# lm3410-sepic-rgb-led-driver-tester-mk-1.net
KiCad netlist of a schematic drawn in EAGLE
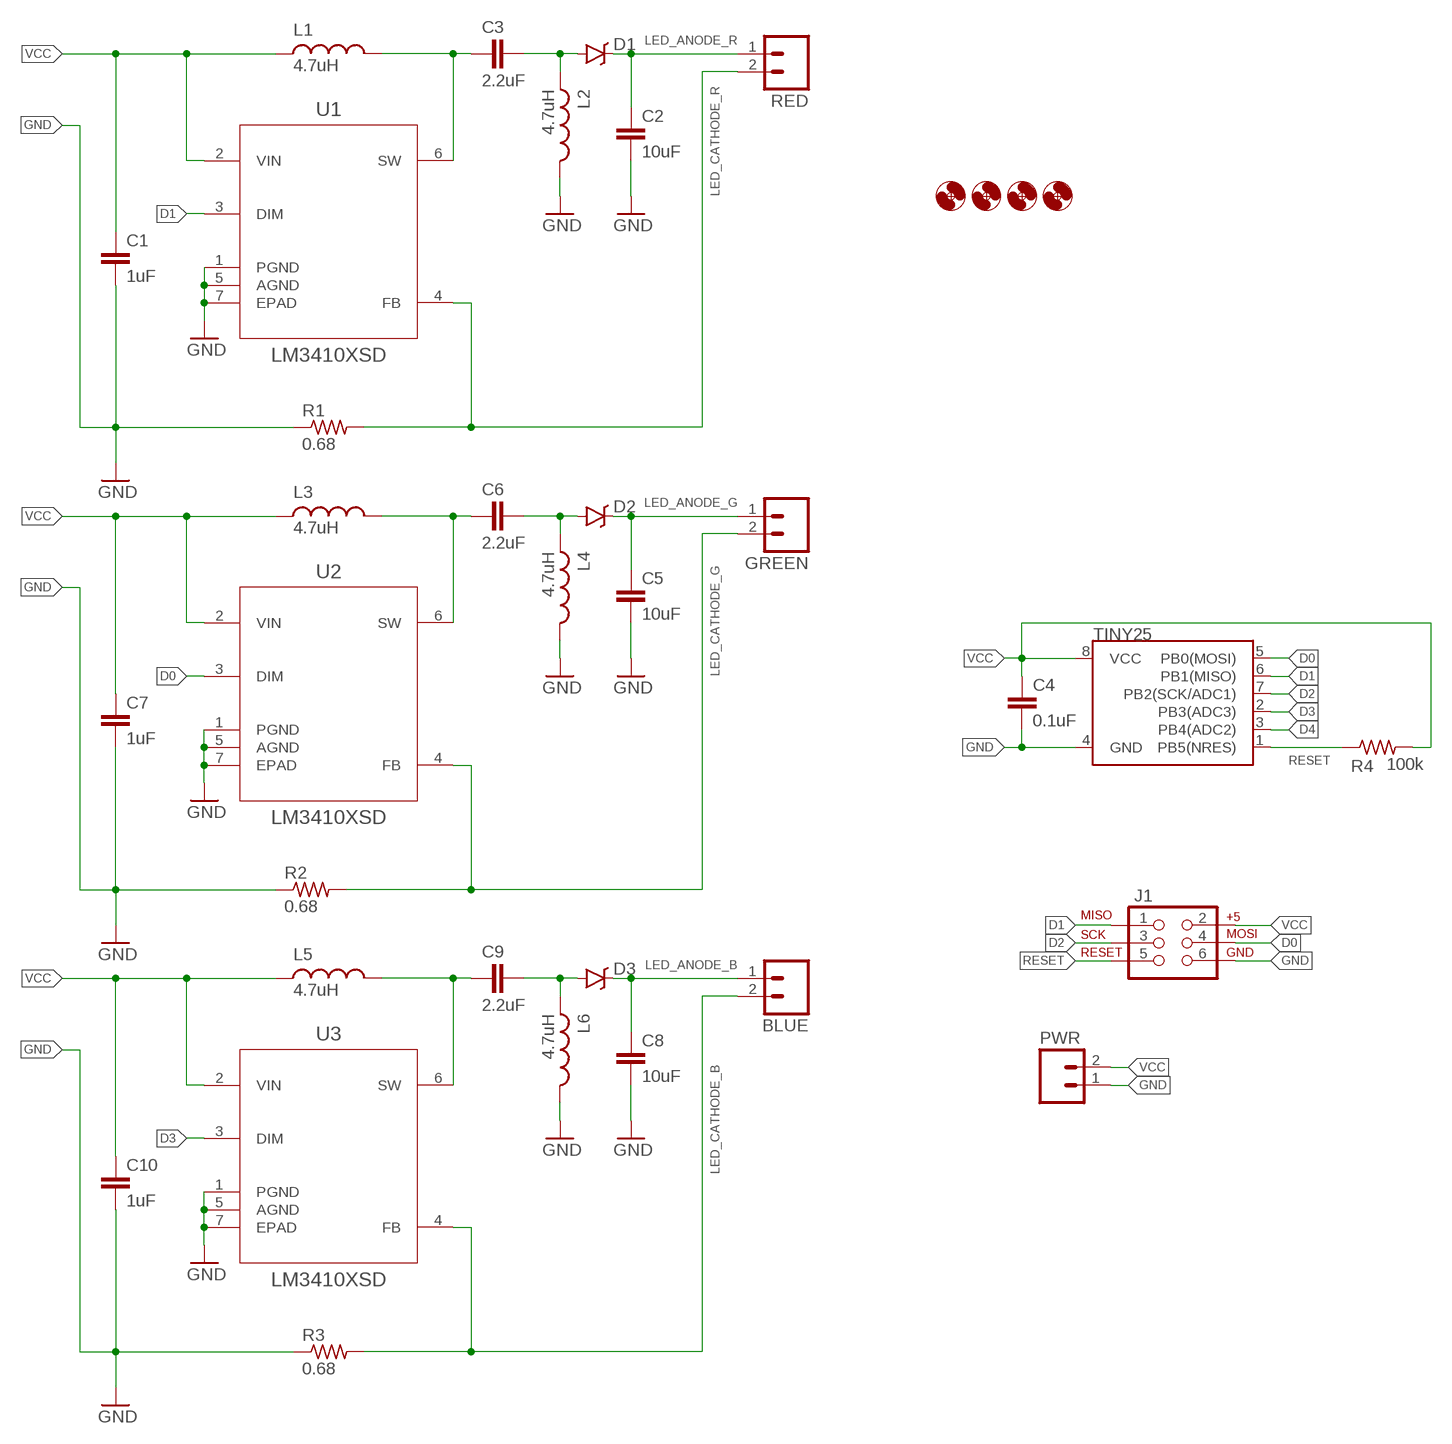
[diagram p0: schematic, sheet 1]

(export (version "E")
  (design (tool "Eeschema 10.0.6"))
  (components
    (comp (ref "BLUE")
      (value "M02JST-PTH-VERT")
      (footprint "eagle-import:JST-2-PH-VERT-PTH")
      (libsource (lib "eagle-import") (part "M02JST-PTH-VERT"))
    )
    (comp (ref "C1")
      (value "1uF")
      (footprint "eagle-import:C0603")
      (libsource (lib "eagle-import") (part "CAPACITOR-CERAMICC0603"))
    )
    (comp (ref "C2")
      (value "10uF")
      (footprint "eagle-import:C0603")
      (libsource (lib "eagle-import") (part "CAPACITOR-CERAMICC0603"))
    )
    (comp (ref "C3")
      (value "2.2uF")
      (footprint "eagle-import:C0805")
      (libsource (lib "eagle-import") (part "CAPACITOR-CERAMICC0805"))
    )
    (comp (ref "C4")
      (value "0.1uF")
      (footprint "eagle-import:C0603")
      (libsource (lib "eagle-import") (part "CAPACITOR-CERAMICC0603"))
    )
    (comp (ref "C5")
      (value "10uF")
      (footprint "eagle-import:C0603")
      (libsource (lib "eagle-import") (part "CAPACITOR-CERAMICC0603"))
    )
    (comp (ref "C6")
      (value "2.2uF")
      (footprint "eagle-import:C0805")
      (libsource (lib "eagle-import") (part "CAPACITOR-CERAMICC0805"))
    )
    (comp (ref "C7")
      (value "1uF")
      (footprint "eagle-import:C0603")
      (libsource (lib "eagle-import") (part "CAPACITOR-CERAMICC0603"))
    )
    (comp (ref "C8")
      (value "10uF")
      (footprint "eagle-import:C0603")
      (libsource (lib "eagle-import") (part "CAPACITOR-CERAMICC0603"))
    )
    (comp (ref "C9")
      (value "2.2uF")
      (footprint "eagle-import:C0805")
      (libsource (lib "eagle-import") (part "CAPACITOR-CERAMICC0805"))
    )
    (comp (ref "C10")
      (value "1uF")
      (footprint "eagle-import:C0603")
      (libsource (lib "eagle-import") (part "CAPACITOR-CERAMICC0603"))
    )
    (comp (ref "D1")
      (value "PMEG4005EJ")
      (footprint "eagle-import:SOD-323")
      (libsource (lib "eagle-import") (part "DIODE-SCHOTTKY-PMEG4005EJ"))
    )
    (comp (ref "D2")
      (value "PMEG4005EJ")
      (footprint "eagle-import:SOD-323")
      (libsource (lib "eagle-import") (part "DIODE-SCHOTTKY-PMEG4005EJ"))
    )
    (comp (ref "D3")
      (value "PMEG4005EJ")
      (footprint "eagle-import:SOD-323")
      (libsource (lib "eagle-import") (part "DIODE-SCHOTTKY-PMEG4005EJ"))
    )
    (comp (ref "GREEN")
      (value "M02JST-PTH-VERT")
      (footprint "eagle-import:JST-2-PH-VERT-PTH")
      (libsource (lib "eagle-import") (part "M02JST-PTH-VERT"))
    )
    (comp (ref "H1")
      (value "HOLE#2")
      (footprint "eagle-import:HOLE-#2")
      (libsource (lib "eagle-import") (part "HOLE#2"))
    )
    (comp (ref "H2")
      (value "HOLE#2")
      (footprint "eagle-import:HOLE-#2")
      (libsource (lib "eagle-import") (part "HOLE#2"))
    )
    (comp (ref "H3")
      (value "HOLE#2")
      (footprint "eagle-import:HOLE-#2")
      (libsource (lib "eagle-import") (part "HOLE#2"))
    )
    (comp (ref "H4")
      (value "HOLE#2")
      (footprint "eagle-import:HOLE-#2")
      (libsource (lib "eagle-import") (part "HOLE#2"))
    )
    (comp (ref "J1")
      (value "AVR_SPI_PRG_6PTH")
      (footprint "eagle-import:2X3")
      (libsource (lib "eagle-import") (part "AVR_SPI_PRG_6PTH"))
    )
    (comp (ref "L1")
      (value "4.7uH")
      (footprint "eagle-import:INDUCTOR_2X1.6MM")
      (libsource (lib "eagle-import") (part "INDUCTORIFSC-0806"))
    )
    (comp (ref "L2")
      (value "4.7uH")
      (footprint "eagle-import:INDUCTOR_2X1.6MM")
      (libsource (lib "eagle-import") (part "INDUCTORIFSC-0806"))
    )
    (comp (ref "L3")
      (value "4.7uH")
      (footprint "eagle-import:INDUCTOR_2X1.6MM")
      (libsource (lib "eagle-import") (part "INDUCTORIFSC-0806"))
    )
    (comp (ref "L4")
      (value "4.7uH")
      (footprint "eagle-import:INDUCTOR_2X1.6MM")
      (libsource (lib "eagle-import") (part "INDUCTORIFSC-0806"))
    )
    (comp (ref "L5")
      (value "4.7uH")
      (footprint "eagle-import:INDUCTOR_2X1.6MM")
      (libsource (lib "eagle-import") (part "INDUCTORIFSC-0806"))
    )
    (comp (ref "L6")
      (value "4.7uH")
      (footprint "eagle-import:INDUCTOR_2X1.6MM")
      (libsource (lib "eagle-import") (part "INDUCTORIFSC-0806"))
    )
    (comp (ref "PWR")
      (value "M02JST-PTH-VERT")
      (footprint "eagle-import:JST-2-PH-VERT-PTH")
      (libsource (lib "eagle-import") (part "M02JST-PTH-VERT"))
    )
    (comp (ref "R1")
      (value "0.68")
      (footprint "eagle-import:R0805")
      (libsource (lib "eagle-import") (part "RESISTORR0805"))
    )
    (comp (ref "R2")
      (value "0.68")
      (footprint "eagle-import:R0805")
      (libsource (lib "eagle-import") (part "RESISTORR0805"))
    )
    (comp (ref "R3")
      (value "0.68")
      (footprint "eagle-import:R0805")
      (libsource (lib "eagle-import") (part "RESISTORR0805"))
    )
    (comp (ref "R4")
      (value "100k")
      (footprint "eagle-import:R0603")
      (libsource (lib "eagle-import") (part "RESISTORR0603"))
    )
    (comp (ref "RED")
      (value "M02JST-PTH-VERT")
      (footprint "eagle-import:JST-2-PH-VERT-PTH")
      (libsource (lib "eagle-import") (part "M02JST-PTH-VERT"))
    )
    (comp (ref "TINY25")
      (value "ATTINY45TINY25-20-SOICN")
      (footprint "eagle-import:SO08")
      (libsource (lib "eagle-import") (part "ATTINY45TINY25-20-SOICN"))
    )
    (comp (ref "U1")
      (value "LM3410XSD")
      (footprint "eagle-import:DFN300X300X80-7N")
      (libsource (lib "eagle-import") (part "LM3410XSD"))
    )
    (comp (ref "U2")
      (value "LM3410XSD")
      (footprint "eagle-import:DFN300X300X80-7N")
      (libsource (lib "eagle-import") (part "LM3410XSD"))
    )
    (comp (ref "U3")
      (value "LM3410XSD")
      (footprint "eagle-import:DFN300X300X80-7N")
      (libsource (lib "eagle-import") (part "LM3410XSD"))
    )
  )
  (nets
    (net (code "1") (name "/LED_ANODE_B") (class "Default")
      (node (ref "BLUE") (pin "1") (pinfunction "1_1") (pintype "passive"))
      (node (ref "C8") (pin "1") (pinfunction "1_1") (pintype "passive"))
      (node (ref "D3") (pin "C") (pinfunction "C_C") (pintype "passive"))
    )
    (net (code "2") (name "/LED_ANODE_G") (class "Default")
      (node (ref "C5") (pin "1") (pinfunction "1_1") (pintype "passive"))
      (node (ref "D2") (pin "C") (pinfunction "C_C") (pintype "passive"))
      (node (ref "GREEN") (pin "1") (pinfunction "1_1") (pintype "passive"))
    )
    (net (code "3") (name "/LED_ANODE_R") (class "Default")
      (node (ref "C2") (pin "1") (pinfunction "1_1") (pintype "passive"))
      (node (ref "D1") (pin "C") (pinfunction "C_C") (pintype "passive"))
      (node (ref "RED") (pin "1") (pinfunction "1_1") (pintype "passive"))
    )
    (net (code "4") (name "/LED_CATHODE_B") (class "Default")
      (node (ref "BLUE") (pin "2") (pinfunction "2_2") (pintype "passive"))
      (node (ref "R3") (pin "2") (pinfunction "2_2") (pintype "passive"))
      (node (ref "U3") (pin "4") (pinfunction "FB_4") (pintype "input"))
    )
    (net (code "5") (name "/LED_CATHODE_G") (class "Default")
      (node (ref "GREEN") (pin "2") (pinfunction "2_2") (pintype "passive"))
      (node (ref "R2") (pin "2") (pinfunction "2_2") (pintype "passive"))
      (node (ref "U2") (pin "4") (pinfunction "FB_4") (pintype "input"))
    )
    (net (code "6") (name "/LED_CATHODE_R") (class "Default")
      (node (ref "R1") (pin "2") (pinfunction "2_2") (pintype "passive"))
      (node (ref "RED") (pin "2") (pinfunction "2_2") (pintype "passive"))
      (node (ref "U1") (pin "4") (pinfunction "FB_4") (pintype "input"))
    )
    (net (code "7") (name "D0") (class "Default")
      (node (ref "J1") (pin "4") (pinfunction "4_4") (pintype "passive"))
      (node (ref "TINY25") (pin "5") (pinfunction "PB0(MOSI)_5") (pintype "bidirectional"))
      (node (ref "U2") (pin "3") (pinfunction "DIM_3") (pintype "input"))
    )
    (net (code "8") (name "D1") (class "Default")
      (node (ref "J1") (pin "1") (pinfunction "1_1") (pintype "passive"))
      (node (ref "TINY25") (pin "6") (pinfunction "PB1(MISO)_6") (pintype "bidirectional"))
      (node (ref "U1") (pin "3") (pinfunction "DIM_3") (pintype "input"))
    )
    (net (code "9") (name "D2") (class "Default")
      (node (ref "J1") (pin "3") (pinfunction "3_3") (pintype "passive"))
      (node (ref "TINY25") (pin "7") (pinfunction "PB2(SCK/ADC1)_7") (pintype "bidirectional"))
    )
    (net (code "10") (name "D3") (class "Default")
      (node (ref "TINY25") (pin "2") (pinfunction "PB3(ADC3)_2") (pintype "bidirectional"))
      (node (ref "U3") (pin "3") (pinfunction "DIM_3") (pintype "input"))
    )
    (net (code "11") (name "D4") (class "Default")
      (node (ref "TINY25") (pin "3") (pinfunction "PB4(ADC2)_3") (pintype "bidirectional"))
    )
    (net (code "12") (name "GND") (class "Default")
      (node (ref "C1") (pin "2") (pinfunction "2_2") (pintype "passive"))
      (node (ref "C10") (pin "2") (pinfunction "2_2") (pintype "passive"))
      (node (ref "C2") (pin "2") (pinfunction "2_2") (pintype "passive"))
      (node (ref "C4") (pin "2") (pinfunction "2_2") (pintype "passive"))
      (node (ref "C5") (pin "2") (pinfunction "2_2") (pintype "passive"))
      (node (ref "C7") (pin "2") (pinfunction "2_2") (pintype "passive"))
      (node (ref "C8") (pin "2") (pinfunction "2_2") (pintype "passive"))
      (node (ref "J1") (pin "6") (pinfunction "6_6") (pintype "passive"))
      (node (ref "L2") (pin "P$2") (pinfunction "2_P$2") (pintype "passive"))
      (node (ref "L4") (pin "P$2") (pinfunction "2_P$2") (pintype "passive"))
      (node (ref "L6") (pin "P$2") (pinfunction "2_P$2") (pintype "passive"))
      (node (ref "PWR") (pin "1") (pinfunction "1_1") (pintype "passive"))
      (node (ref "R1") (pin "1") (pinfunction "1_1") (pintype "passive"))
      (node (ref "R2") (pin "1") (pinfunction "1_1") (pintype "passive"))
      (node (ref "R3") (pin "1") (pinfunction "1_1") (pintype "passive"))
      (node (ref "TINY25") (pin "4") (pinfunction "GND_4") (pintype "bidirectional"))
      (node (ref "U1") (pin "1") (pinfunction "PGND_1") (pintype "passive"))
      (node (ref "U1") (pin "5") (pinfunction "AGND_5") (pintype "passive"))
      (node (ref "U1") (pin "7") (pinfunction "EPAD_7") (pintype "passive"))
      (node (ref "U2") (pin "1") (pinfunction "PGND_1") (pintype "passive"))
      (node (ref "U2") (pin "5") (pinfunction "AGND_5") (pintype "passive"))
      (node (ref "U2") (pin "7") (pinfunction "EPAD_7") (pintype "passive"))
      (node (ref "U3") (pin "1") (pinfunction "PGND_1") (pintype "passive"))
      (node (ref "U3") (pin "5") (pinfunction "AGND_5") (pintype "passive"))
      (node (ref "U3") (pin "7") (pinfunction "EPAD_7") (pintype "passive"))
    )
    (net (code "13") (name "Net-(L1-2)") (class "Default")
      (node (ref "C3") (pin "1") (pinfunction "1_1") (pintype "passive"))
      (node (ref "L1") (pin "P$2") (pinfunction "2_P$2") (pintype "passive"))
      (node (ref "U1") (pin "6") (pinfunction "SW_6") (pintype "output"))
    )
    (net (code "14") (name "Net-(L2-1)") (class "Default")
      (node (ref "C3") (pin "2") (pinfunction "2_2") (pintype "passive"))
      (node (ref "D1") (pin "A") (pinfunction "A_A") (pintype "passive"))
      (node (ref "L2") (pin "P$1") (pinfunction "1_P$1") (pintype "passive"))
    )
    (net (code "15") (name "Net-(L3-2)") (class "Default")
      (node (ref "C6") (pin "1") (pinfunction "1_1") (pintype "passive"))
      (node (ref "L3") (pin "P$2") (pinfunction "2_P$2") (pintype "passive"))
      (node (ref "U2") (pin "6") (pinfunction "SW_6") (pintype "output"))
    )
    (net (code "16") (name "Net-(L4-1)") (class "Default")
      (node (ref "C6") (pin "2") (pinfunction "2_2") (pintype "passive"))
      (node (ref "D2") (pin "A") (pinfunction "A_A") (pintype "passive"))
      (node (ref "L4") (pin "P$1") (pinfunction "1_P$1") (pintype "passive"))
    )
    (net (code "17") (name "Net-(L5-2)") (class "Default")
      (node (ref "C9") (pin "1") (pinfunction "1_1") (pintype "passive"))
      (node (ref "L5") (pin "P$2") (pinfunction "2_P$2") (pintype "passive"))
      (node (ref "U3") (pin "6") (pinfunction "SW_6") (pintype "output"))
    )
    (net (code "18") (name "Net-(L6-1)") (class "Default")
      (node (ref "C9") (pin "2") (pinfunction "2_2") (pintype "passive"))
      (node (ref "D3") (pin "A") (pinfunction "A_A") (pintype "passive"))
      (node (ref "L6") (pin "P$1") (pinfunction "1_P$1") (pintype "passive"))
    )
    (net (code "19") (name "RESET") (class "Default")
      (node (ref "J1") (pin "5") (pinfunction "5_5") (pintype "passive"))
      (node (ref "R4") (pin "1") (pinfunction "1_1") (pintype "passive"))
      (node (ref "TINY25") (pin "1") (pinfunction "PB5(NRES)_1") (pintype "bidirectional"))
    )
    (net (code "20") (name "VCC") (class "Default")
      (node (ref "C1") (pin "1") (pinfunction "1_1") (pintype "passive"))
      (node (ref "C10") (pin "1") (pinfunction "1_1") (pintype "passive"))
      (node (ref "C4") (pin "1") (pinfunction "1_1") (pintype "passive"))
      (node (ref "C7") (pin "1") (pinfunction "1_1") (pintype "passive"))
      (node (ref "J1") (pin "2") (pinfunction "2_2") (pintype "passive"))
      (node (ref "L1") (pin "P$1") (pinfunction "1_P$1") (pintype "passive"))
      (node (ref "L3") (pin "P$1") (pinfunction "1_P$1") (pintype "passive"))
      (node (ref "L5") (pin "P$1") (pinfunction "1_P$1") (pintype "passive"))
      (node (ref "PWR") (pin "2") (pinfunction "2_2") (pintype "passive"))
      (node (ref "R4") (pin "2") (pinfunction "2_2") (pintype "passive"))
      (node (ref "TINY25") (pin "8") (pinfunction "VCC_8") (pintype "bidirectional"))
      (node (ref "U1") (pin "2") (pinfunction "VIN_2") (pintype "power_in"))
      (node (ref "U2") (pin "2") (pinfunction "VIN_2") (pintype "power_in"))
      (node (ref "U3") (pin "2") (pinfunction "VIN_2") (pintype "power_in"))
    )
  )
)
